# Schematic.net
KiCad netlist of a schematic drawn in EAGLE
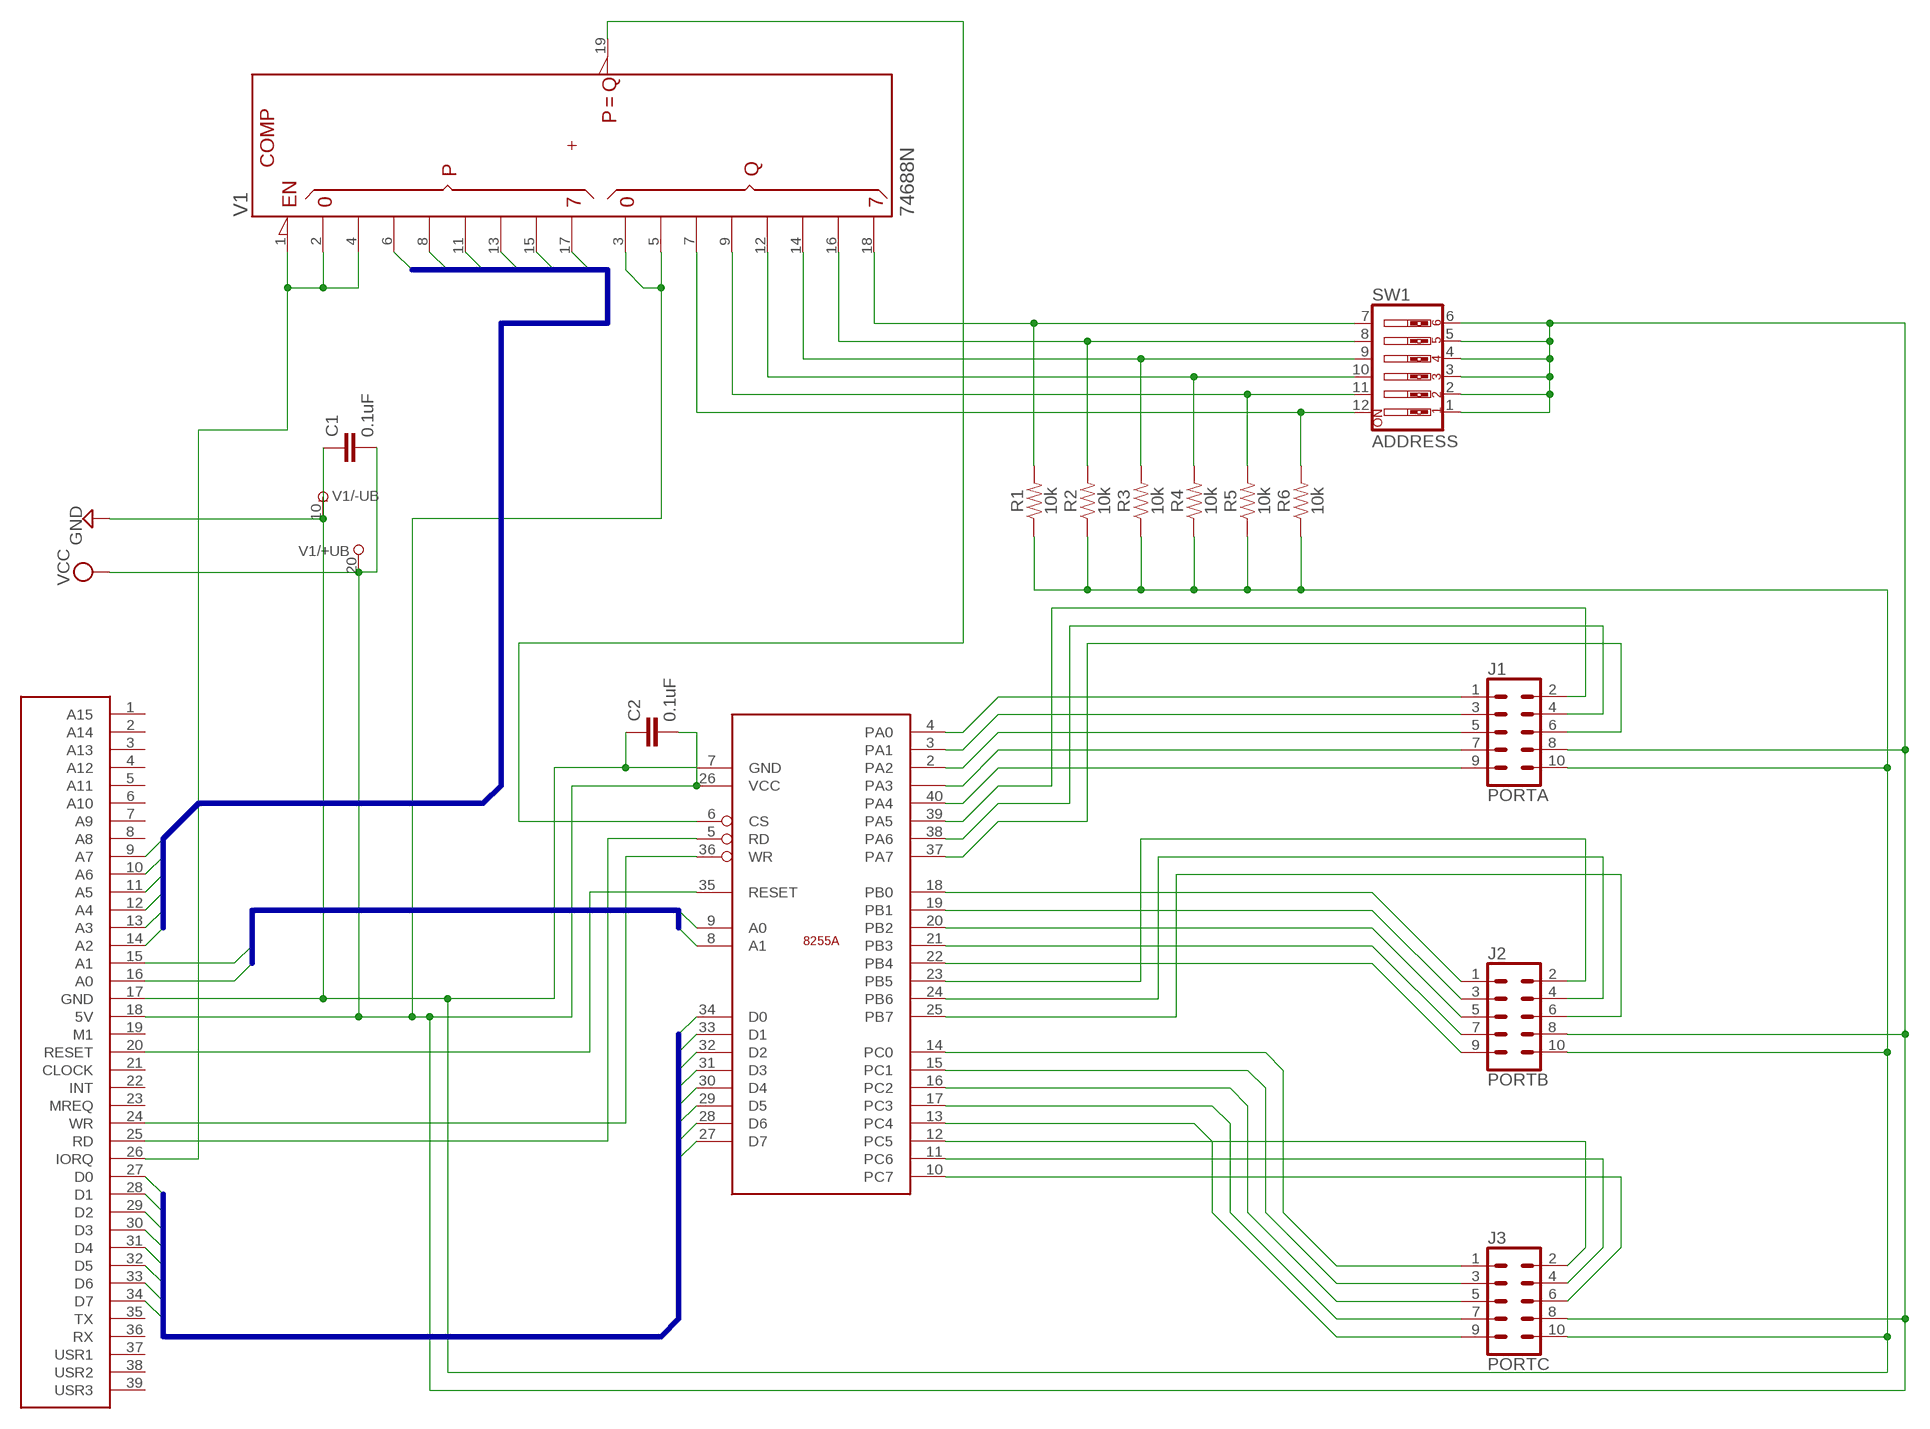
[diagram p0: schematic, sheet 1]

(export (version "E")
  (design (tool "Eeschema 10.0.6"))
  (components
    (comp (ref "C1")
      (value "0.1uF")
      (footprint "eagle-import:CAP-PTH-SMALL-KIT")
      (libsource (lib "eagle-import") (part "0.1UF-KIT-EZ-50V-20%"))
    )
    (comp (ref "C2")
      (value "0.1uF")
      (footprint "eagle-import:CAP-PTH-SMALL-KIT")
      (libsource (lib "eagle-import") (part "0.1UF-KIT-EZ-50V-20%"))
    )
    (comp (ref "J1")
      (value "PORTA")
      (footprint "eagle-import:2X5-SHROUDED")
      (libsource (lib "eagle-import") (part "CONN_05X2SHD"))
    )
    (comp (ref "J2")
      (value "PORTB")
      (footprint "eagle-import:2X5-SHROUDED")
      (libsource (lib "eagle-import") (part "CONN_05X2SHD"))
    )
    (comp (ref "J3")
      (value "PORTC")
      (footprint "eagle-import:2X5-SHROUDED")
      (libsource (lib "eagle-import") (part "CONN_05X2SHD"))
    )
    (comp (ref "R1")
      (value "10k")
      (footprint "eagle-import:AXIAL-0.3")
      (libsource (lib "eagle-import") (part "10KOHM-HORIZ-1/4W-1%"))
    )
    (comp (ref "R2")
      (value "10k")
      (footprint "eagle-import:AXIAL-0.3")
      (libsource (lib "eagle-import") (part "10KOHM-HORIZ-1/4W-1%"))
    )
    (comp (ref "R3")
      (value "10k")
      (footprint "eagle-import:AXIAL-0.3")
      (libsource (lib "eagle-import") (part "10KOHM-HORIZ-1/4W-1%"))
    )
    (comp (ref "R4")
      (value "10k")
      (footprint "eagle-import:AXIAL-0.3")
      (libsource (lib "eagle-import") (part "10KOHM-HORIZ-1/4W-1%"))
    )
    (comp (ref "R5")
      (value "10k")
      (footprint "eagle-import:AXIAL-0.3")
      (libsource (lib "eagle-import") (part "10KOHM-HORIZ-1/4W-1%"))
    )
    (comp (ref "R6")
      (value "10k")
      (footprint "eagle-import:AXIAL-0.3")
      (libsource (lib "eagle-import") (part "10KOHM-HORIZ-1/4W-1%"))
    )
    (comp (ref "SW1")
      (value "ADDRESS")
      (footprint "eagle-import:EDG-06")
      (libsource (lib "eagle-import") (part "SW_DIP-6"))
    )
    (comp (ref "U$1")
      (value "RC2014BUS")
      (footprint "eagle-import:RC2014BUS")
      (libsource (lib "eagle-import") (part "RC2014BUS"))
    )
    (comp (ref "U$2")
      (value "8255")
      (footprint "eagle-import:8255")
      (libsource (lib "eagle-import") (part "8255"))
    )
    (comp (ref "V1")
      (value "74688N")
      (footprint "eagle-import:DIL20")
      (libsource (lib "eagle-import") (part "74688N"))
    )
  )
  (nets
    (net (code "1") (name "/ADRBUS0") (class "Default")
      (node (ref "U$1") (pin "14") (pinfunction "A2_14") (pintype "bidirectional"))
      (node (ref "U$1") (pin "15") (pinfunction "A1_15") (pintype "bidirectional"))
      (node (ref "U$1") (pin "16") (pinfunction "A0_16") (pintype "bidirectional"))
      (node (ref "U$2") (pin "9") (pinfunction "A0_9") (pintype "bidirectional"))
      (node (ref "V1") (pin "6") (pinfunction "P2_6") (pintype "input"))
    )
    (net (code "2") (name "/ADRBUS1") (class "Default")
      (node (ref "U$1") (pin "13") (pinfunction "A3_13") (pintype "bidirectional"))
      (node (ref "U$2") (pin "8") (pinfunction "A1_8") (pintype "bidirectional"))
      (node (ref "V1") (pin "8") (pinfunction "P3_8") (pintype "input"))
    )
    (net (code "3") (name "/ADRBUS2") (class "Default")
      (node (ref "U$1") (pin "12") (pinfunction "A4_12") (pintype "bidirectional"))
      (node (ref "V1") (pin "11") (pinfunction "P4_11") (pintype "input"))
    )
    (net (code "4") (name "/ADRBUS3") (class "Default")
      (node (ref "U$1") (pin "11") (pinfunction "A5_11") (pintype "bidirectional"))
      (node (ref "V1") (pin "13") (pinfunction "P5_13") (pintype "input"))
    )
    (net (code "5") (name "/ADRBUS4") (class "Default")
      (node (ref "U$1") (pin "10") (pinfunction "A6_10") (pintype "bidirectional"))
      (node (ref "V1") (pin "15") (pinfunction "P6_15") (pintype "input"))
    )
    (net (code "6") (name "/ADRBUS5") (class "Default")
      (node (ref "U$1") (pin "9") (pinfunction "A7_9") (pintype "bidirectional"))
      (node (ref "V1") (pin "17") (pinfunction "P7_17") (pintype "input"))
    )
    (net (code "7") (name "/DATABUS0") (class "Default")
      (node (ref "U$1") (pin "27") (pinfunction "D0_27") (pintype "bidirectional"))
      (node (ref "U$2") (pin "34") (pinfunction "D0_34") (pintype "bidirectional"))
    )
    (net (code "8") (name "/DATABUS1") (class "Default")
      (node (ref "U$1") (pin "28") (pinfunction "D1_28") (pintype "bidirectional"))
      (node (ref "U$2") (pin "33") (pinfunction "D1_33") (pintype "bidirectional"))
    )
    (net (code "9") (name "/DATABUS2") (class "Default")
      (node (ref "U$1") (pin "29") (pinfunction "D2_29") (pintype "bidirectional"))
      (node (ref "U$2") (pin "32") (pinfunction "D2_32") (pintype "bidirectional"))
    )
    (net (code "10") (name "/DATABUS3") (class "Default")
      (node (ref "U$1") (pin "30") (pinfunction "D3_30") (pintype "bidirectional"))
      (node (ref "U$2") (pin "31") (pinfunction "D3_31") (pintype "bidirectional"))
    )
    (net (code "11") (name "/DATABUS4") (class "Default")
      (node (ref "U$1") (pin "31") (pinfunction "D4_31") (pintype "bidirectional"))
      (node (ref "U$2") (pin "30") (pinfunction "D4_30") (pintype "bidirectional"))
    )
    (net (code "12") (name "/DATABUS5") (class "Default")
      (node (ref "U$1") (pin "32") (pinfunction "D5_32") (pintype "bidirectional"))
      (node (ref "U$2") (pin "29") (pinfunction "D5_29") (pintype "bidirectional"))
    )
    (net (code "13") (name "/DATABUS6") (class "Default")
      (node (ref "U$1") (pin "33") (pinfunction "D6_33") (pintype "bidirectional"))
      (node (ref "U$2") (pin "28") (pinfunction "D6_28") (pintype "bidirectional"))
    )
    (net (code "14") (name "/DATABUS7") (class "Default")
      (node (ref "U$1") (pin "34") (pinfunction "D7_34") (pintype "bidirectional"))
      (node (ref "U$2") (pin "27") (pinfunction "D7_27") (pintype "bidirectional"))
    )
    (net (code "15") (name "GND") (class "Default")
      (node (ref "C1") (pin "1") (pinfunction "1_1") (pintype "passive"))
      (node (ref "C2") (pin "1") (pinfunction "1_1") (pintype "passive"))
      (node (ref "J1") (pin "10") (pinfunction "10_10") (pintype "passive"))
      (node (ref "J2") (pin "10") (pinfunction "10_10") (pintype "passive"))
      (node (ref "J3") (pin "10") (pinfunction "10_10") (pintype "passive"))
      (node (ref "R1") (pin "P$1") (pinfunction "1_P$1") (pintype "passive"))
      (node (ref "R2") (pin "P$1") (pinfunction "1_P$1") (pintype "passive"))
      (node (ref "R3") (pin "P$1") (pinfunction "1_P$1") (pintype "passive"))
      (node (ref "R4") (pin "P$1") (pinfunction "1_P$1") (pintype "passive"))
      (node (ref "R5") (pin "P$1") (pinfunction "1_P$1") (pintype "passive"))
      (node (ref "R6") (pin "P$1") (pinfunction "1_P$1") (pintype "passive"))
      (node (ref "U$1") (pin "17") (pinfunction "GND_17") (pintype "bidirectional"))
      (node (ref "U$2") (pin "7") (pinfunction "GND_7") (pintype "bidirectional"))
      (node (ref "V1") (pin "10") (pinfunction "-UB_10") (pintype "power_in"))
    )
    (net (code "16") (name "Net-(R1-2)") (class "Default")
      (node (ref "R1") (pin "P$2") (pinfunction "2_P$2") (pintype "passive"))
      (node (ref "SW1") (pin "7") (pinfunction "7_7") (pintype "passive"))
      (node (ref "V1") (pin "18") (pinfunction "Q7_18") (pintype "input"))
    )
    (net (code "17") (name "Net-(R2-2)") (class "Default")
      (node (ref "R2") (pin "P$2") (pinfunction "2_P$2") (pintype "passive"))
      (node (ref "SW1") (pin "8") (pinfunction "8_8") (pintype "passive"))
      (node (ref "V1") (pin "16") (pinfunction "Q6_16") (pintype "input"))
    )
    (net (code "18") (name "Net-(R3-2)") (class "Default")
      (node (ref "R3") (pin "P$2") (pinfunction "2_P$2") (pintype "passive"))
      (node (ref "SW1") (pin "9") (pinfunction "9_9") (pintype "passive"))
      (node (ref "V1") (pin "14") (pinfunction "Q5_14") (pintype "input"))
    )
    (net (code "19") (name "Net-(R4-2)") (class "Default")
      (node (ref "R4") (pin "P$2") (pinfunction "2_P$2") (pintype "passive"))
      (node (ref "SW1") (pin "10") (pinfunction "10_10") (pintype "passive"))
      (node (ref "V1") (pin "12") (pinfunction "Q4_12") (pintype "input"))
    )
    (net (code "20") (name "Net-(R5-2)") (class "Default")
      (node (ref "R5") (pin "P$2") (pinfunction "2_P$2") (pintype "passive"))
      (node (ref "SW1") (pin "11") (pinfunction "11_11") (pintype "passive"))
      (node (ref "V1") (pin "9") (pinfunction "Q3_9") (pintype "input"))
    )
    (net (code "21") (name "Net-(R6-2)") (class "Default")
      (node (ref "R6") (pin "P$2") (pinfunction "2_P$2") (pintype "passive"))
      (node (ref "SW1") (pin "12") (pinfunction "12_12") (pintype "passive"))
      (node (ref "V1") (pin "7") (pinfunction "Q2_7") (pintype "input"))
    )
    (net (code "22") (name "Net-(U$1-IORQ)") (class "Default")
      (node (ref "U$1") (pin "26") (pinfunction "IORQ_26") (pintype "bidirectional"))
      (node (ref "V1") (pin "1") (pinfunction "~{G}_1") (pintype "input"))
      (node (ref "V1") (pin "2") (pinfunction "P0_2") (pintype "input"))
      (node (ref "V1") (pin "4") (pinfunction "P1_4") (pintype "input"))
    )
    (net (code "23") (name "Net-(U$1-RD)") (class "Default")
      (node (ref "U$1") (pin "25") (pinfunction "RD_25") (pintype "bidirectional"))
      (node (ref "U$2") (pin "5") (pinfunction "RD_5") (pintype "bidirectional"))
    )
    (net (code "24") (name "Net-(U$1-RESET)") (class "Default")
      (node (ref "U$1") (pin "20") (pinfunction "RESET_20") (pintype "bidirectional"))
      (node (ref "U$2") (pin "35") (pinfunction "RESET_35") (pintype "bidirectional"))
    )
    (net (code "25") (name "Net-(U$1-WR)") (class "Default")
      (node (ref "U$1") (pin "24") (pinfunction "WR_24") (pintype "bidirectional"))
      (node (ref "U$2") (pin "36") (pinfunction "WR_36") (pintype "bidirectional"))
    )
    (net (code "26") (name "Net-(U$2-CS)") (class "Default")
      (node (ref "U$2") (pin "6") (pinfunction "CS_6") (pintype "bidirectional"))
      (node (ref "V1") (pin "19") (pinfunction "~{P=Q}_19") (pintype "output"))
    )
    (net (code "27") (name "Net-(U$2-PA0)") (class "Default")
      (node (ref "J1") (pin "1") (pinfunction "1_1") (pintype "passive"))
      (node (ref "U$2") (pin "4") (pinfunction "PA0_4") (pintype "bidirectional"))
    )
    (net (code "28") (name "Net-(U$2-PA1)") (class "Default")
      (node (ref "J1") (pin "3") (pinfunction "3_3") (pintype "passive"))
      (node (ref "U$2") (pin "3") (pinfunction "PA1_3") (pintype "bidirectional"))
    )
    (net (code "29") (name "Net-(U$2-PA2)") (class "Default")
      (node (ref "J1") (pin "5") (pinfunction "5_5") (pintype "passive"))
      (node (ref "U$2") (pin "2") (pinfunction "PA2_2") (pintype "bidirectional"))
    )
    (net (code "30") (name "Net-(U$2-PA3)") (class "Default")
      (node (ref "J1") (pin "7") (pinfunction "7_7") (pintype "passive"))
      (node (ref "U$2") (pin "1") (pinfunction "PA3_1") (pintype "input"))
    )
    (net (code "31") (name "Net-(U$2-PA4)") (class "Default")
      (node (ref "J1") (pin "9") (pinfunction "9_9") (pintype "passive"))
      (node (ref "U$2") (pin "40") (pinfunction "PA4_40") (pintype "bidirectional"))
    )
    (net (code "32") (name "Net-(U$2-PA5)") (class "Default")
      (node (ref "J1") (pin "2") (pinfunction "2_2") (pintype "passive"))
      (node (ref "U$2") (pin "39") (pinfunction "PA5_39") (pintype "bidirectional"))
    )
    (net (code "33") (name "Net-(U$2-PA6)") (class "Default")
      (node (ref "J1") (pin "4") (pinfunction "4_4") (pintype "passive"))
      (node (ref "U$2") (pin "38") (pinfunction "PA6_38") (pintype "bidirectional"))
    )
    (net (code "34") (name "Net-(U$2-PA7)") (class "Default")
      (node (ref "J1") (pin "6") (pinfunction "6_6") (pintype "passive"))
      (node (ref "U$2") (pin "37") (pinfunction "PA7_37") (pintype "bidirectional"))
    )
    (net (code "35") (name "Net-(U$2-PB0)") (class "Default")
      (node (ref "J2") (pin "1") (pinfunction "1_1") (pintype "passive"))
      (node (ref "U$2") (pin "18") (pinfunction "PB0_18") (pintype "bidirectional"))
    )
    (net (code "36") (name "Net-(U$2-PB1)") (class "Default")
      (node (ref "J2") (pin "3") (pinfunction "3_3") (pintype "passive"))
      (node (ref "U$2") (pin "19") (pinfunction "PB1_19") (pintype "bidirectional"))
    )
    (net (code "37") (name "Net-(U$2-PB2)") (class "Default")
      (node (ref "J2") (pin "5") (pinfunction "5_5") (pintype "passive"))
      (node (ref "U$2") (pin "20") (pinfunction "PB2_20") (pintype "bidirectional"))
    )
    (net (code "38") (name "Net-(U$2-PB3)") (class "Default")
      (node (ref "J2") (pin "7") (pinfunction "7_7") (pintype "passive"))
      (node (ref "U$2") (pin "21") (pinfunction "PB3_21") (pintype "bidirectional"))
    )
    (net (code "39") (name "Net-(U$2-PB4)") (class "Default")
      (node (ref "J2") (pin "9") (pinfunction "9_9") (pintype "passive"))
      (node (ref "U$2") (pin "22") (pinfunction "PB4_22") (pintype "bidirectional"))
    )
    (net (code "40") (name "Net-(U$2-PB5)") (class "Default")
      (node (ref "J2") (pin "2") (pinfunction "2_2") (pintype "passive"))
      (node (ref "U$2") (pin "23") (pinfunction "PB5_23") (pintype "bidirectional"))
    )
    (net (code "41") (name "Net-(U$2-PB6)") (class "Default")
      (node (ref "J2") (pin "4") (pinfunction "4_4") (pintype "passive"))
      (node (ref "U$2") (pin "24") (pinfunction "PB6_24") (pintype "bidirectional"))
    )
    (net (code "42") (name "Net-(U$2-PB7)") (class "Default")
      (node (ref "J2") (pin "6") (pinfunction "6_6") (pintype "passive"))
      (node (ref "U$2") (pin "25") (pinfunction "PB7_25") (pintype "bidirectional"))
    )
    (net (code "43") (name "Net-(U$2-PC0)") (class "Default")
      (node (ref "J3") (pin "1") (pinfunction "1_1") (pintype "passive"))
      (node (ref "U$2") (pin "14") (pinfunction "PC0_14") (pintype "bidirectional"))
    )
    (net (code "44") (name "Net-(U$2-PC1)") (class "Default")
      (node (ref "J3") (pin "3") (pinfunction "3_3") (pintype "passive"))
      (node (ref "U$2") (pin "15") (pinfunction "PC1_15") (pintype "bidirectional"))
    )
    (net (code "45") (name "Net-(U$2-PC2)") (class "Default")
      (node (ref "J3") (pin "5") (pinfunction "5_5") (pintype "passive"))
      (node (ref "U$2") (pin "16") (pinfunction "PC2_16") (pintype "bidirectional"))
    )
    (net (code "46") (name "Net-(U$2-PC3)") (class "Default")
      (node (ref "J3") (pin "7") (pinfunction "7_7") (pintype "passive"))
      (node (ref "U$2") (pin "17") (pinfunction "PC3_17") (pintype "bidirectional"))
    )
    (net (code "47") (name "Net-(U$2-PC4)") (class "Default")
      (node (ref "J3") (pin "9") (pinfunction "9_9") (pintype "passive"))
      (node (ref "U$2") (pin "13") (pinfunction "PC4_13") (pintype "bidirectional"))
    )
    (net (code "48") (name "Net-(U$2-PC5)") (class "Default")
      (node (ref "J3") (pin "2") (pinfunction "2_2") (pintype "passive"))
      (node (ref "U$2") (pin "12") (pinfunction "PC5_12") (pintype "bidirectional"))
    )
    (net (code "49") (name "Net-(U$2-PC6)") (class "Default")
      (node (ref "J3") (pin "4") (pinfunction "4_4") (pintype "passive"))
      (node (ref "U$2") (pin "11") (pinfunction "PC6_11") (pintype "bidirectional"))
    )
    (net (code "50") (name "Net-(U$2-PC7)") (class "Default")
      (node (ref "J3") (pin "6") (pinfunction "6_6") (pintype "passive"))
      (node (ref "U$2") (pin "10") (pinfunction "PC7_10") (pintype "bidirectional"))
    )
    (net (code "51") (name "VCC") (class "Default")
      (node (ref "C1") (pin "2") (pinfunction "2_2") (pintype "passive"))
      (node (ref "C2") (pin "2") (pinfunction "2_2") (pintype "passive"))
      (node (ref "J1") (pin "8") (pinfunction "8_8") (pintype "passive"))
      (node (ref "J2") (pin "8") (pinfunction "8_8") (pintype "passive"))
      (node (ref "J3") (pin "8") (pinfunction "8_8") (pintype "passive"))
      (node (ref "SW1") (pin "1") (pinfunction "1_1") (pintype "passive"))
      (node (ref "SW1") (pin "2") (pinfunction "2_2") (pintype "passive"))
      (node (ref "SW1") (pin "3") (pinfunction "3_3") (pintype "passive"))
      (node (ref "SW1") (pin "4") (pinfunction "4_4") (pintype "passive"))
      (node (ref "SW1") (pin "5") (pinfunction "5_5") (pintype "passive"))
      (node (ref "SW1") (pin "6") (pinfunction "6_6") (pintype "passive"))
      (node (ref "U$1") (pin "18") (pinfunction "5V_18") (pintype "bidirectional"))
      (node (ref "U$2") (pin "26") (pinfunction "VCC_26") (pintype "bidirectional"))
      (node (ref "V1") (pin "20") (pinfunction "+UB_20") (pintype "power_in"))
      (node (ref "V1") (pin "3") (pinfunction "Q0_3") (pintype "input"))
      (node (ref "V1") (pin "5") (pinfunction "Q1_5") (pintype "input"))
    )
    (net (code "52") (name "unconnected-(U$1-A8-Pad8)") (class "Default")
      (node (ref "U$1") (pin "8") (pinfunction "A8_8") (pintype "bidirectional"))
    )
    (net (code "53") (name "unconnected-(U$1-A9-Pad7)") (class "Default")
      (node (ref "U$1") (pin "7") (pinfunction "A9_7") (pintype "bidirectional"))
    )
    (net (code "54") (name "unconnected-(U$1-A10-Pad6)") (class "Default")
      (node (ref "U$1") (pin "6") (pinfunction "A10_6") (pintype "bidirectional"))
    )
    (net (code "55") (name "unconnected-(U$1-A11-Pad5)") (class "Default")
      (node (ref "U$1") (pin "5") (pinfunction "A11_5") (pintype "bidirectional"))
    )
    (net (code "56") (name "unconnected-(U$1-A12-Pad4)") (class "Default")
      (node (ref "U$1") (pin "4") (pinfunction "A12_4") (pintype "bidirectional"))
    )
    (net (code "57") (name "unconnected-(U$1-A13-Pad3)") (class "Default")
      (node (ref "U$1") (pin "3") (pinfunction "A13_3") (pintype "bidirectional"))
    )
    (net (code "58") (name "unconnected-(U$1-A14-Pad2)") (class "Default")
      (node (ref "U$1") (pin "2") (pinfunction "A14_2") (pintype "bidirectional"))
    )
    (net (code "59") (name "unconnected-(U$1-A15-Pad1)") (class "Default")
      (node (ref "U$1") (pin "1") (pinfunction "A15_1") (pintype "bidirectional"))
    )
    (net (code "60") (name "unconnected-(U$1-CLOCK-Pad21)") (class "Default")
      (node (ref "U$1") (pin "21") (pinfunction "CLOCK_21") (pintype "bidirectional"))
    )
    (net (code "61") (name "unconnected-(U$1-INT-Pad22)") (class "Default")
      (node (ref "U$1") (pin "22") (pinfunction "INT_22") (pintype "bidirectional"))
    )
    (net (code "62") (name "unconnected-(U$1-M1-Pad19)") (class "Default")
      (node (ref "U$1") (pin "19") (pinfunction "M1_19") (pintype "bidirectional"))
    )
    (net (code "63") (name "unconnected-(U$1-MREQ-Pad23)") (class "Default")
      (node (ref "U$1") (pin "23") (pinfunction "MREQ_23") (pintype "bidirectional"))
    )
    (net (code "64") (name "unconnected-(U$1-RX-Pad36)") (class "Default")
      (node (ref "U$1") (pin "36") (pinfunction "RX_36") (pintype "bidirectional"))
    )
    (net (code "65") (name "unconnected-(U$1-TX-Pad35)") (class "Default")
      (node (ref "U$1") (pin "35") (pinfunction "TX_35") (pintype "bidirectional"))
    )
    (net (code "66") (name "unconnected-(U$1-USR1-Pad37)") (class "Default")
      (node (ref "U$1") (pin "37") (pinfunction "USR1_37") (pintype "bidirectional"))
    )
    (net (code "67") (name "unconnected-(U$1-USR2-Pad38)") (class "Default")
      (node (ref "U$1") (pin "38") (pinfunction "USR2_38") (pintype "bidirectional"))
    )
    (net (code "68") (name "unconnected-(U$1-USR3-Pad39)") (class "Default")
      (node (ref "U$1") (pin "39") (pinfunction "USR3_39") (pintype "bidirectional"))
    )
  )
)
